# pca63519_-_Power.net
KiCad netlist of a schematic drawn in Altium Designer
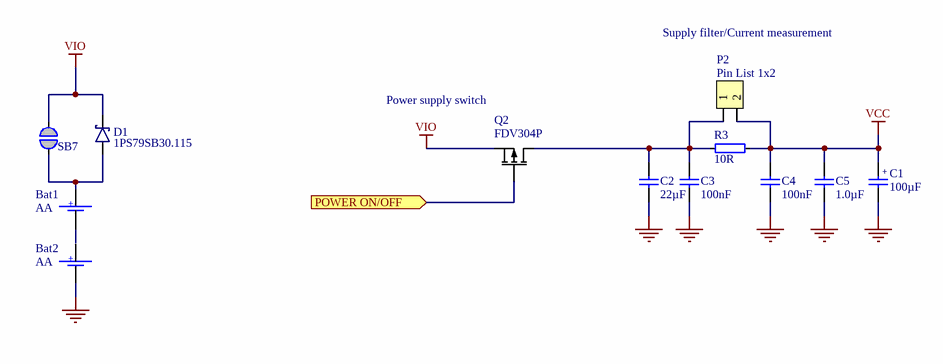
[diagram p0: pca63519 - Power.SchDoc]

(export (version "E")
  (design (tool "Eeschema 10.0.6"))
  (components
    (comp (ref "Bat1")
      (value "AA")
      (footprint "POLSATBATTERYHOLDER")
      (description "Polsat Battery holder, Positive pole")
      (fields
        (field (name "PART NUMBER") "POLSATBATTERYHOLDER_P")
        (field (name "MANUFACTURER") "PolSat")
        (field (name "PUBLISHER") "Nordic Semiconductor")
      )
      (libsource (lib "Nordic Passive DB") (part "Battery - P"))
    )
    (comp (ref "Bat2")
      (value "AA")
      (footprint "POLSATBATTERYHOLDER")
      (description "Polsat Battery holder, Negative pole")
      (fields
        (field (name "PART NUMBER") "POLSATBATTERYHOLDER_N")
        (field (name "MANUFACTURER") "PolSat")
        (field (name "PUBLISHER") "Nordic Semiconductor")
      )
      (libsource (lib "Nordic Passive DB") (part "Battery - N"))
    )
    (comp (ref "C1")
      (value "100µF")
      (footprint "CAPMP3528X21N")
      (description "Capacitor, Tantalum, ±10%")
      (fields
        (field (name "PART NUMBER") "C3528-100µF")
        (field (name "MANUFACTURER") "Vishay Sprague")
        (field (name "PUBLISHER") "Nordic Semiconductor")
      )
      (libsource (lib "Nordic Passive DB") (part "CAP_TAN"))
    )
    (comp (ref "C2")
      (value "22µF")
      (footprint "CAPC2012X11L")
      (description "Capacitor, X5R, ±10%")
      (fields (field (name "PART NUMBER") "C0805-22µ") (field (name "PUBLISHER") "Nordic Semiconductor"))
      (libsource (lib "Nordic Passive DB") (part "CAP"))
    )
    (comp (ref "C3")
      (value "100nF")
      (footprint "CAPC1005X04L")
      (description "Capacitor, X7R, ±10%")
      (fields (field (name "PART NUMBER") "C0402-100n") (field (name "PUBLISHER") "Nordic Semiconductor"))
      (libsource (lib "Nordic Passive DB") (part "CAP"))
    )
    (comp (ref "C4")
      (value "100nF")
      (footprint "CAPC1005X04L")
      (description "Capacitor, X7R, ±10%")
      (fields (field (name "PART NUMBER") "C0402-100n") (field (name "PUBLISHER") "Nordic Semiconductor"))
      (libsource (lib "Nordic Passive DB") (part "CAP"))
    )
    (comp (ref "C5")
      (value "1.0µF")
      (footprint "CAPC1005X04L")
      (description "Capacitor, X5R, ±5%")
      (fields (field (name "PART NUMBER") "C0402-1µ0") (field (name "PUBLISHER") "Nordic Semiconductor"))
      (libsource (lib "Nordic Passive DB") (part "CAP"))
    )
    (comp (ref "D1")
      (value "1PS79SB30.115")
      (footprint "SOD-523")
      (description "Diode Schottky Vf=0.38, Vr=40V, If=200mA, Ir=500nA")
      (fields
        (field (name "MANUFACTURER") "NXP")
        (field (name "2ND SOURCE PART NUMBER") "873-4097")
        (field (name "PUBLISHER") "Nordic Semiconductor")
      )
      (libsource (lib "Nordic Discrete DB") (part "D{colon}SCHOTTKY"))
    )
    (comp (ref "P2")
      (value "Pin List 1x2")
      (footprint "LIST_1x2")
      (description "Pin List 1x2, 2.54mm (100mil)")
      (fields (field (name "PUBLISHER") "Nordic Semiconductor"))
      (libsource (lib "Nordic Passive DB") (part "CONN-2"))
    )
    (comp (ref "Q2")
      (value "FDV304P")
      (footprint "SOT-23a")
      (description "Mosfet FDV304P")
      (fields
        (field (name "2ND SOURCE PART NUMBER") "FDV304PCT-ND")
        (field (name "PUBLISHER") "Nordic Semiconductor")
      )
      (libsource (lib "Nordic Discrete DB") (part "T{colon}FET-P"))
    )
    (comp (ref "R3")
      (value "10R")
      (footprint "RESC1005X04L")
      (description "Resistor, ±1%, 0.063W")
      (fields (field (name "PART NUMBER") "R0402-10R") (field (name "PUBLISHER") "Nordic Semiconductor"))
      (libsource (lib "Nordic Passive DB") (part "RES_1"))
    )
    (comp (ref "SB7")
      (value "Solderbridge")
      (footprint "Solderbridge_0.4")
      (fields
        (field (name "PART NUMBER") "Solderbridge 0.4mm")
        (field (name "PUBLISHER") "Nordic Semiconductor")
      )
      (libsource (lib "Nordic Passive DB") (part "SOLDERBRIDGE"))
    )
  )
  (nets
    (net (code "1") (name "/POWER ON{slash}OFF") (class "Default")
      (node (ref "Q2") (pin "1") (pinfunction "G_1") (pintype "passive"))
    )
    (net (code "2") (name "GND") (class "Default")
      (node (ref "Bat2") (pin "1") (pintype "passive"))
      (node (ref "C1") (pin "2") (pinfunction "2_2") (pintype "passive"))
      (node (ref "C2") (pin "1") (pinfunction "1_1") (pintype "passive"))
      (node (ref "C3") (pin "1") (pinfunction "1_1") (pintype "passive"))
      (node (ref "C4") (pin "1") (pinfunction "1_1") (pintype "passive"))
      (node (ref "C5") (pin "1") (pinfunction "1_1") (pintype "passive"))
    )
    (net (code "3") (name "Net-(D1-A)") (class "Default")
      (node (ref "Bat1") (pin "1") (pintype "passive"))
      (node (ref "D1") (pin "1") (pinfunction "A_1") (pintype "passive"))
      (node (ref "SB7") (pin "2") (pinfunction "1_2") (pintype "passive"))
    )
    (net (code "4") (name "Net-(Q2-D)") (class "Default")
      (node (ref "C2") (pin "2") (pinfunction "2_2") (pintype "passive"))
      (node (ref "C3") (pin "2") (pinfunction "2_2") (pintype "passive"))
      (node (ref "P2") (pin "1") (pinfunction "1_1") (pintype "passive"))
      (node (ref "Q2") (pin "3") (pinfunction "D_3") (pintype "passive"))
      (node (ref "R3") (pin "1") (pinfunction "1_1") (pintype "passive"))
    )
    (net (code "5") (name "VCC") (class "Default")
      (node (ref "C1") (pin "1") (pinfunction "1_1") (pintype "passive"))
      (node (ref "C4") (pin "2") (pinfunction "2_2") (pintype "passive"))
      (node (ref "C5") (pin "2") (pinfunction "2_2") (pintype "passive"))
      (node (ref "P2") (pin "2") (pinfunction "2_2") (pintype "passive"))
      (node (ref "R3") (pin "2") (pinfunction "2_2") (pintype "passive"))
    )
    (net (code "6") (name "VIO") (class "Default")
      (node (ref "D1") (pin "3") (pinfunction "C_3") (pintype "passive"))
      (node (ref "Q2") (pin "2") (pinfunction "S_2") (pintype "passive"))
      (node (ref "SB7") (pin "1") (pinfunction "0_1") (pintype "passive"))
    )
  )
)
